# Elan_Chip_Interface.net
KiCad netlist of a schematic drawn in Altium Designer
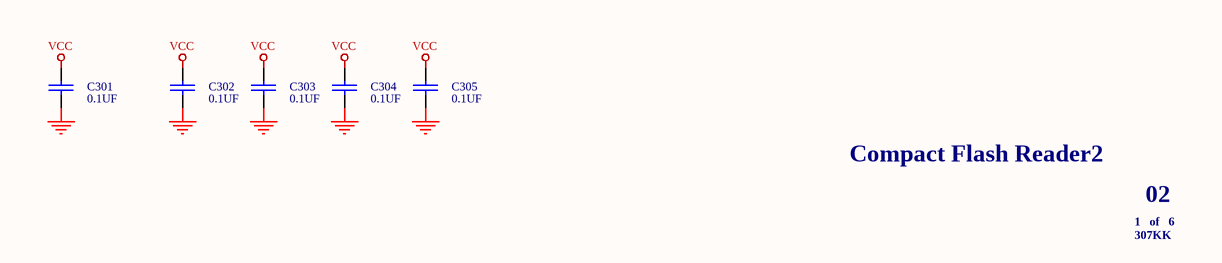
[diagram p0: Elan Chip Interface.schdoc]

(export (version "E")
  (design (tool "Eeschema 10.0.6"))
  (components
    (comp (ref "C301")
      (value "0.1UF")
      (footprint "0603")
      (description "Capacitor")
      (libsource (lib "*") (part "CAP"))
    )
    (comp (ref "C302")
      (value "0.1UF")
      (footprint "0603")
      (description "Capacitor")
      (libsource (lib "*") (part "CAP"))
    )
    (comp (ref "C303")
      (value "0.1UF")
      (footprint "0603")
      (description "Capacitor")
      (libsource (lib "*") (part "CAP"))
    )
    (comp (ref "C304")
      (value "0.1UF")
      (footprint "0603")
      (description "Capacitor")
      (libsource (lib "*") (part "CAP"))
    )
    (comp (ref "C305")
      (value "0.1UF")
      (footprint "0603")
      (description "Capacitor")
      (libsource (lib "*") (part "CAP"))
    )
  )
  (nets
    (net (code "1") (name "GND_COM") (class "Default")
      (node (ref "C301") (pin "2") (pinfunction "2_2") (pintype "passive"))
      (node (ref "C302") (pin "2") (pinfunction "2_2") (pintype "passive"))
      (node (ref "C303") (pin "2") (pinfunction "2_2") (pintype "passive"))
      (node (ref "C304") (pin "2") (pinfunction "2_2") (pintype "passive"))
      (node (ref "C305") (pin "2") (pinfunction "2_2") (pintype "passive"))
    )
    (net (code "2") (name "VCC") (class "Default")
      (node (ref "C301") (pin "1") (pinfunction "1_1") (pintype "passive"))
      (node (ref "C302") (pin "1") (pinfunction "1_1") (pintype "passive"))
      (node (ref "C303") (pin "1") (pinfunction "1_1") (pintype "passive"))
      (node (ref "C304") (pin "1") (pinfunction "1_1") (pintype "passive"))
      (node (ref "C305") (pin "1") (pinfunction "1_1") (pintype "passive"))
    )
  )
)
